# sch_version2.net
KiCad netlist of a schematic drawn in Altium Designer
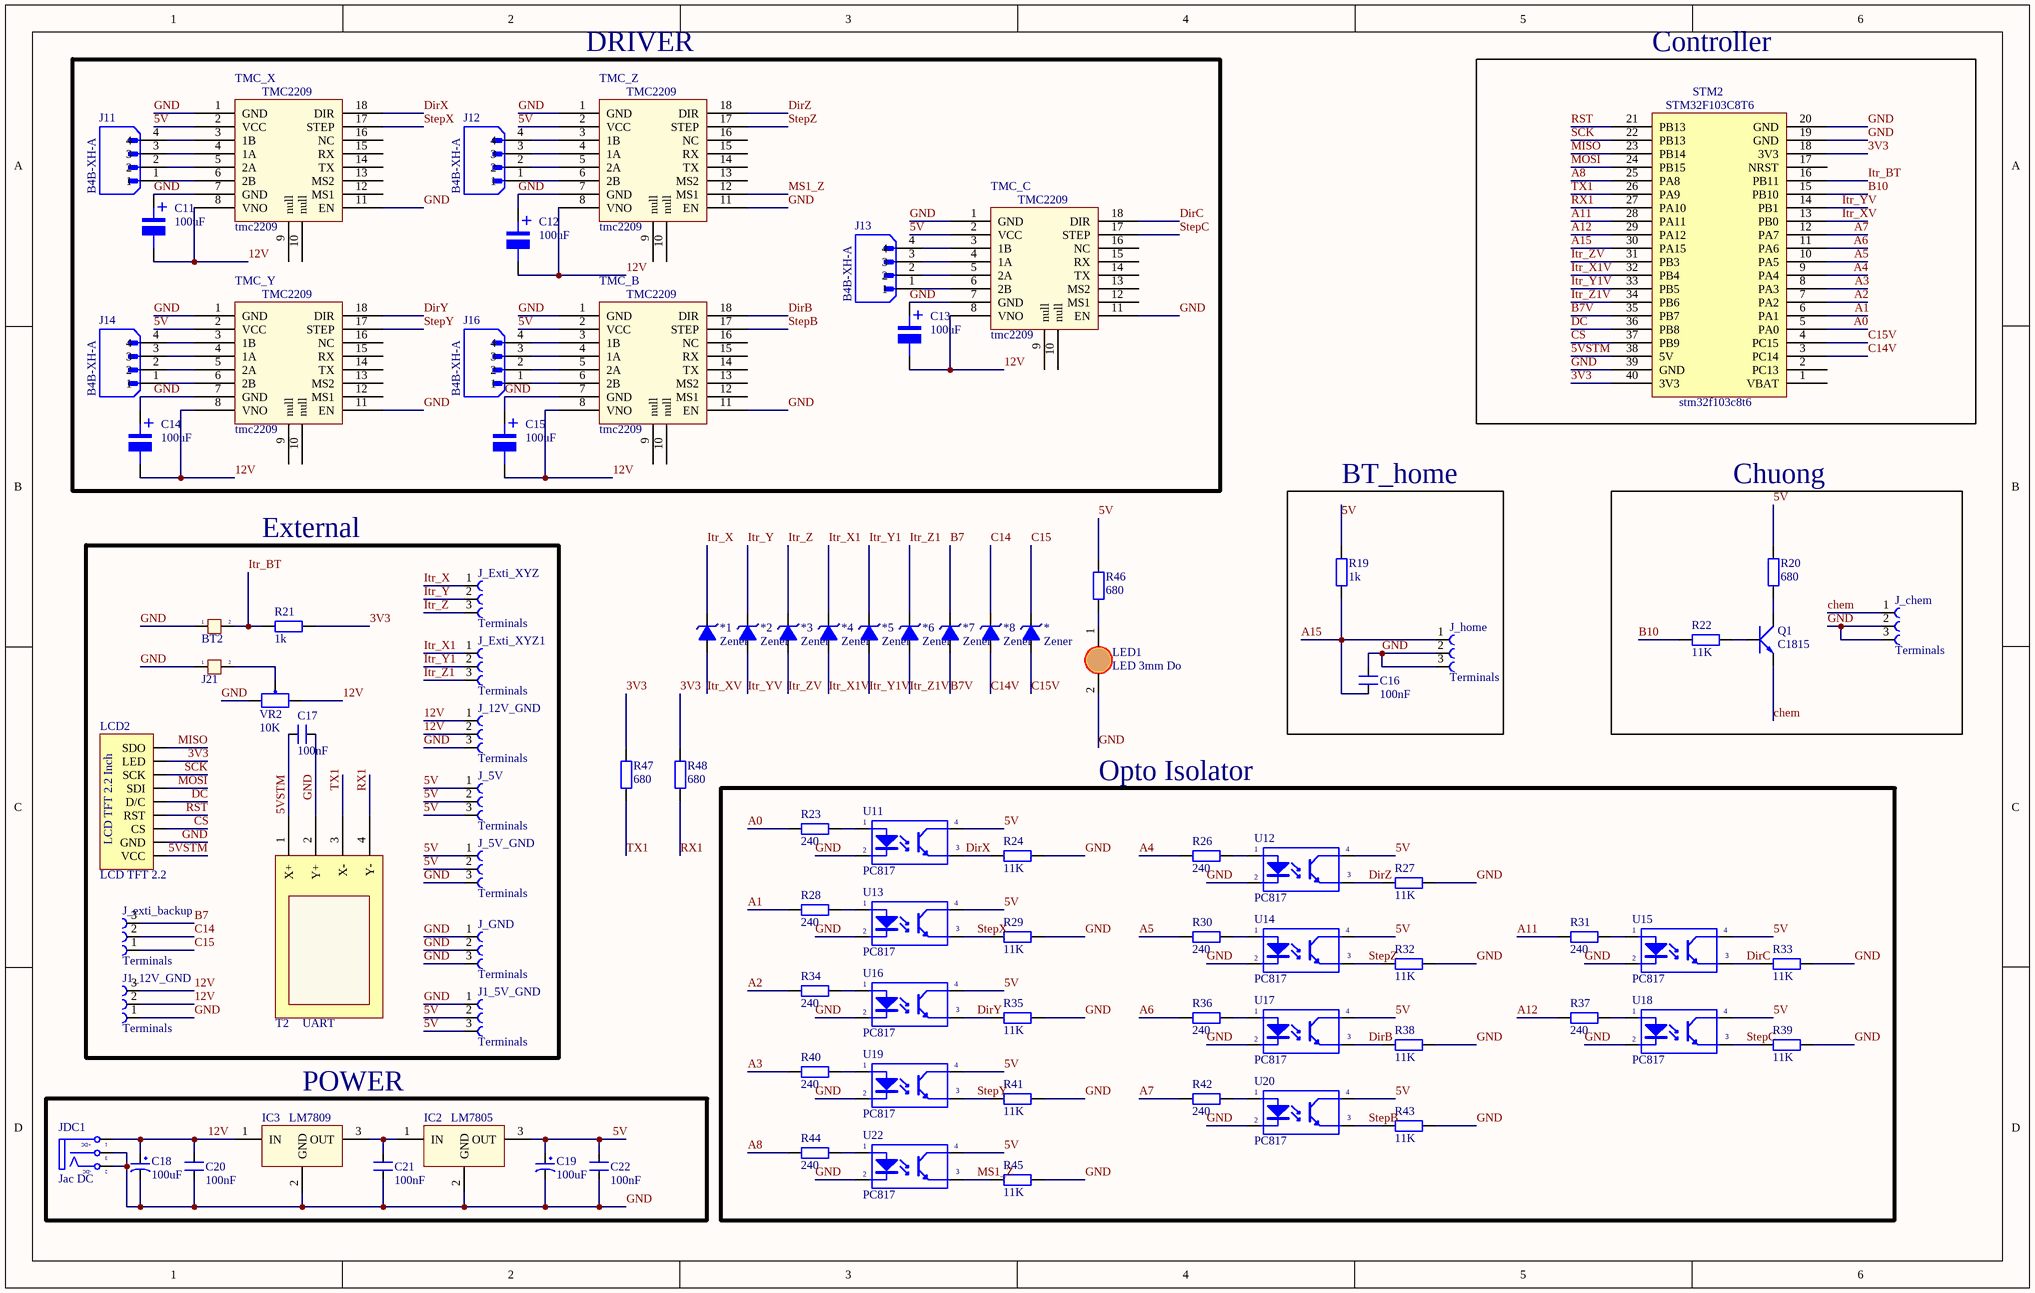
[diagram p0: sch_version2.SchDoc]

(export (version "E")
  (design (tool "Eeschema 10.0.6"))
  (components
    (comp (ref "*") (value "Zener") (footprint "D1A") (libsource (lib "syhaunguyen") (part "Zener")))
    (comp (ref "*1") (value "Zener") (footprint "D1A") (libsource (lib "syhaunguyen") (part "Zener")))
    (comp (ref "*2") (value "Zener") (footprint "D1A") (libsource (lib "syhaunguyen") (part "Zener")))
    (comp (ref "*3") (value "Zener") (footprint "D1A") (libsource (lib "syhaunguyen") (part "Zener")))
    (comp (ref "*4") (value "Zener") (footprint "D1A") (libsource (lib "syhaunguyen") (part "Zener")))
    (comp (ref "*5") (value "Zener") (footprint "D1A") (libsource (lib "syhaunguyen") (part "Zener")))
    (comp (ref "*6") (value "Zener") (footprint "D1A") (libsource (lib "syhaunguyen") (part "Zener")))
    (comp (ref "*7") (value "Zener") (footprint "D1A") (libsource (lib "syhaunguyen") (part "Zener")))
    (comp (ref "*8") (value "Zener") (footprint "D1A") (libsource (lib "syhaunguyen") (part "Zener")))
    (comp (ref "BT2") (value "Jumper 2") (footprint "jp2h") (libsource (lib "My Library") (part "JP 2")))
    (comp (ref "C11")
      (value "100uF")
      (footprint "tu nhom 6.3 (d)")
      (description "Dán")
      (libsource (lib "THU VIEN SCH") (part "Tu Nhom 100uF 16V"))
    )
    (comp (ref "C12")
      (value "100uF")
      (footprint "tu nhom 6.3 (d)")
      (description "Dán")
      (libsource (lib "THU VIEN SCH") (part "Tu Nhom 100uF 16V"))
    )
    (comp (ref "C13")
      (value "100uF")
      (footprint "tu nhom 6.3 (d)")
      (description "Dán")
      (libsource (lib "THU VIEN SCH") (part "Tu Nhom 100uF 16V"))
    )
    (comp (ref "C14")
      (value "100uF")
      (footprint "tu nhom 6.3 (d)")
      (description "Dán")
      (libsource (lib "THU VIEN SCH") (part "Tu Nhom 100uF 16V"))
    )
    (comp (ref "C15")
      (value "100uF")
      (footprint "tu nhom 6.3 (d)")
      (description "Dán")
      (libsource (lib "THU VIEN SCH") (part "Tu Nhom 100uF 16V"))
    )
    (comp (ref "C16")
      (value "100nF")
      (footprint "CN2")
      (description "Cap np 104 => 105pF")
      (libsource (lib "My Library") (part "CN2"))
    )
    (comp (ref "C17")
      (value "100nF")
      (footprint "CN2")
      (description "Cap np 104 => 105pF")
      (libsource (lib "My Library") (part "CN2"))
    )
    (comp (ref "C18")
      (value "100uF")
      (footprint "CP1.5/3.4")
      (description "Cap 100uF/35V - 470uF/16V")
      (libsource (lib "My Library") (part "CP3"))
    )
    (comp (ref "C19")
      (value "100uF")
      (footprint "CP1.5/3.4")
      (description "Cap 100uF/35V - 470uF/16V")
      (libsource (lib "My Library") (part "CP3"))
    )
    (comp (ref "C20")
      (value "100nF")
      (footprint "CN2")
      (description "Cap np 104 => 105pF")
      (libsource (lib "My Library") (part "CN2"))
    )
    (comp (ref "C21")
      (value "100nF")
      (footprint "CN2")
      (description "Cap np 104 => 105pF")
      (libsource (lib "My Library") (part "CN2"))
    )
    (comp (ref "C22")
      (value "100nF")
      (footprint "CN2")
      (description "Cap np 104 => 105pF")
      (libsource (lib "My Library") (part "CN2"))
    )
    (comp (ref "IC2")
      (value "LM7805")
      (footprint "QTO-220")
      (description "On ap +, from + 5 to + 24VDC")
      (libsource (lib "My Library") (part "LM78xx"))
    )
    (comp (ref "IC3")
      (value "LM7809")
      (footprint "QTO-220")
      (description "On ap +, from + 5 to + 24VDC")
      (libsource (lib "My Library") (part "LM78xx"))
    )
    (comp (ref "J1_5V_GND")
      (value "Terminals")
      (footprint "691214110003")
      (description "3 Position Wire to Board Terminal Block Horizontal with Board 0.138 (3.50mm) Through Hole")
      (fields (field (name "MP") "691214110003") (field (name "MF") "Wurth Elektronik"))
      (libsource (lib "691214110003") (part "691214110003"))
    )
    (comp (ref "J1_12V_GND")
      (value "Terminals")
      (footprint "691214110003")
      (description "3 Position Wire to Board Terminal Block Horizontal with Board 0.138 (3.50mm) Through Hole")
      (fields (field (name "MP") "691214110003") (field (name "MF") "Wurth Elektronik"))
      (libsource (lib "691214110003") (part "691214110003"))
    )
    (comp (ref "J11")
      (value "B4B-XH-A")
      (footprint "JST_B4B-XH-A(LF)(SN)")
      (fields (field (name "MP") "B4B-XH-A(LF)(SN)"))
      (libsource (lib "B4B-XH-A_LF__SN_") (part "B4B-XH-A(LF)(SN)"))
    )
    (comp (ref "J12")
      (value "B4B-XH-A")
      (footprint "JST_B4B-XH-A(LF)(SN)")
      (fields (field (name "MP") "B4B-XH-A(LF)(SN)"))
      (libsource (lib "B4B-XH-A_LF__SN_") (part "B4B-XH-A(LF)(SN)"))
    )
    (comp (ref "J13")
      (value "B4B-XH-A")
      (footprint "JST_B4B-XH-A(LF)(SN)")
      (fields (field (name "MP") "B4B-XH-A(LF)(SN)"))
      (libsource (lib "B4B-XH-A_LF__SN_") (part "B4B-XH-A(LF)(SN)"))
    )
    (comp (ref "J14")
      (value "B4B-XH-A")
      (footprint "JST_B4B-XH-A(LF)(SN)")
      (fields (field (name "MP") "B4B-XH-A(LF)(SN)"))
      (libsource (lib "B4B-XH-A_LF__SN_") (part "B4B-XH-A(LF)(SN)"))
    )
    (comp (ref "J16")
      (value "B4B-XH-A")
      (footprint "JST_B4B-XH-A(LF)(SN)")
      (fields (field (name "MP") "B4B-XH-A(LF)(SN)"))
      (libsource (lib "B4B-XH-A_LF__SN_") (part "B4B-XH-A(LF)(SN)"))
    )
    (comp (ref "J21") (value "Jumper 2") (footprint "jp2h") (libsource (lib "syhaunguyen") (part "JP 2")))
    (comp (ref "JDC1")
      (value "Jac DC")
      (footprint "DC-IN")
      (description "Jac DC input")
      (libsource (lib "My Library") (part "DCIN"))
    )
    (comp (ref "J_5V")
      (value "Terminals")
      (footprint "691214110003")
      (description "3 Position Wire to Board Terminal Block Horizontal with Board 0.138 (3.50mm) Through Hole")
      (fields (field (name "MP") "691214110003") (field (name "MF") "Wurth Elektronik"))
      (libsource (lib "691214110003") (part "691214110003"))
    )
    (comp (ref "J_5V_GND")
      (value "Terminals")
      (footprint "691214110003")
      (description "3 Position Wire to Board Terminal Block Horizontal with Board 0.138 (3.50mm) Through Hole")
      (fields (field (name "MP") "691214110003") (field (name "MF") "Wurth Elektronik"))
      (libsource (lib "691214110003") (part "691214110003"))
    )
    (comp (ref "J_12V_GND")
      (value "Terminals")
      (footprint "691214110003")
      (description "3 Position Wire to Board Terminal Block Horizontal with Board 0.138 (3.50mm) Through Hole")
      (fields (field (name "MP") "691214110003") (field (name "MF") "Wurth Elektronik"))
      (libsource (lib "691214110003") (part "691214110003"))
    )
    (comp (ref "J_chem")
      (value "Terminals")
      (footprint "691214110003")
      (description "3 Position Wire to Board Terminal Block Horizontal with Board 0.138 (3.50mm) Through Hole")
      (fields (field (name "MP") "691214110003") (field (name "MF") "Wurth Elektronik"))
      (libsource (lib "691214110003") (part "691214110003"))
    )
    (comp (ref "J_exti_backup")
      (value "Terminals")
      (footprint "691214110003")
      (description "3 Position Wire to Board Terminal Block Horizontal with Board 0.138 (3.50mm) Through Hole")
      (fields (field (name "MP") "691214110003") (field (name "MF") "Wurth Elektronik"))
      (libsource (lib "691214110003") (part "691214110003"))
    )
    (comp (ref "J_Exti_XYZ")
      (value "Terminals")
      (footprint "691214110003")
      (description "3 Position Wire to Board Terminal Block Horizontal with Board 0.138 (3.50mm) Through Hole")
      (fields (field (name "MP") "691214110003") (field (name "MF") "Wurth Elektronik"))
      (libsource (lib "691214110003") (part "691214110003"))
    )
    (comp (ref "J_Exti_XYZ1")
      (value "Terminals")
      (footprint "691214110003")
      (description "3 Position Wire to Board Terminal Block Horizontal with Board 0.138 (3.50mm) Through Hole")
      (fields (field (name "MP") "691214110003") (field (name "MF") "Wurth Elektronik"))
      (libsource (lib "691214110003") (part "691214110003"))
    )
    (comp (ref "J_GND")
      (value "Terminals")
      (footprint "691214110003")
      (description "3 Position Wire to Board Terminal Block Horizontal with Board 0.138 (3.50mm) Through Hole")
      (fields (field (name "MP") "691214110003") (field (name "MF") "Wurth Elektronik"))
      (libsource (lib "691214110003") (part "691214110003"))
    )
    (comp (ref "J_home")
      (value "Terminals")
      (footprint "691214110003")
      (description "3 Position Wire to Board Terminal Block Horizontal with Board 0.138 (3.50mm) Through Hole")
      (fields (field (name "MP") "691214110003") (field (name "MF") "Wurth Elektronik"))
      (libsource (lib "691214110003") (part "691214110003"))
    )
    (comp (ref "LCD2")
      (value "LCD TFT 2.2")
      (footprint "JP9-C1T")
      (fields
        (field (name "MANUFACTURER") "Würth Elektronik eiSos GmbH")
        (field (name "PARTNO") "613009143121")
        (field (name "CREATED BY") "Karrer Zheng")
      )
      (libsource (lib "My Library") (part "LCD TFT 2.2"))
    )
    (comp (ref "LED1")
      (value "LED 3mm Do")
      (footprint "LED 3mm Do")
      (description "Cắm")
      (libsource (lib "THU VIEN SCH") (part "LED 3mm Do"))
    )
    (comp (ref "Q1")
      (value "C1815")
      (footprint "QTO-92")
      (description "NPN 600mW, ECB")
      (libsource (lib "syhaunguyen") (part "C1815"))
    )
    (comp (ref "R19")
      (value "1k")
      (footprint "R1/4W")
      (description "Resistor 1/4W")
      (libsource (lib "My Library") (part "R1/4W"))
    )
    (comp (ref "R20")
      (value "680")
      (footprint "R1/4W")
      (description "Resistor 1/4W")
      (libsource (lib "My Library") (part "R1/4W"))
    )
    (comp (ref "R21")
      (value "1k")
      (footprint "R1/4W")
      (description "Resistor 1/4W")
      (libsource (lib "My Library") (part "R1/4W"))
    )
    (comp (ref "R22")
      (value "11K")
      (footprint "R1/4W")
      (description "Resistor 1/4W")
      (libsource (lib "My Library") (part "R1/4W"))
    )
    (comp (ref "R23")
      (value "240")
      (footprint "R1/4W")
      (description "Resistor 1/4W")
      (libsource (lib "My Library") (part "R1/4W"))
    )
    (comp (ref "R24")
      (value "11K")
      (footprint "R1/4W")
      (description "Resistor 1/4W")
      (libsource (lib "My Library") (part "R1/4W"))
    )
    (comp (ref "R26")
      (value "240")
      (footprint "R1/4W")
      (description "Resistor 1/4W")
      (libsource (lib "My Library") (part "R1/4W"))
    )
    (comp (ref "R27")
      (value "11K")
      (footprint "R1/4W")
      (description "Resistor 1/4W")
      (libsource (lib "My Library") (part "R1/4W"))
    )
    (comp (ref "R28")
      (value "240")
      (footprint "R1/4W")
      (description "Resistor 1/4W")
      (libsource (lib "My Library") (part "R1/4W"))
    )
    (comp (ref "R29")
      (value "11K")
      (footprint "R1/4W")
      (description "Resistor 1/4W")
      (libsource (lib "My Library") (part "R1/4W"))
    )
    (comp (ref "R30")
      (value "240")
      (footprint "R1/4W")
      (description "Resistor 1/4W")
      (libsource (lib "My Library") (part "R1/4W"))
    )
    (comp (ref "R31")
      (value "240")
      (footprint "R1/4W")
      (description "Resistor 1/4W")
      (libsource (lib "My Library") (part "R1/4W"))
    )
    (comp (ref "R32")
      (value "11K")
      (footprint "R1/4W")
      (description "Resistor 1/4W")
      (libsource (lib "My Library") (part "R1/4W"))
    )
    (comp (ref "R33")
      (value "11K")
      (footprint "R1/4W")
      (description "Resistor 1/4W")
      (libsource (lib "My Library") (part "R1/4W"))
    )
    (comp (ref "R34")
      (value "240")
      (footprint "R1/4W")
      (description "Resistor 1/4W")
      (libsource (lib "My Library") (part "R1/4W"))
    )
    (comp (ref "R35")
      (value "11K")
      (footprint "R1/4W")
      (description "Resistor 1/4W")
      (libsource (lib "My Library") (part "R1/4W"))
    )
    (comp (ref "R36")
      (value "240")
      (footprint "R1/4W")
      (description "Resistor 1/4W")
      (libsource (lib "My Library") (part "R1/4W"))
    )
    (comp (ref "R37")
      (value "240")
      (footprint "R1/4W")
      (description "Resistor 1/4W")
      (libsource (lib "My Library") (part "R1/4W"))
    )
    (comp (ref "R38")
      (value "11K")
      (footprint "R1/4W")
      (description "Resistor 1/4W")
      (libsource (lib "My Library") (part "R1/4W"))
    )
    (comp (ref "R39")
      (value "11K")
      (footprint "R1/4W")
      (description "Resistor 1/4W")
      (libsource (lib "My Library") (part "R1/4W"))
    )
    (comp (ref "R40")
      (value "240")
      (footprint "R1/4W")
      (description "Resistor 1/4W")
      (libsource (lib "My Library") (part "R1/4W"))
    )
    (comp (ref "R41")
      (value "11K")
      (footprint "R1/4W")
      (description "Resistor 1/4W")
      (libsource (lib "My Library") (part "R1/4W"))
    )
    (comp (ref "R42")
      (value "240")
      (footprint "R1/4W")
      (description "Resistor 1/4W")
      (libsource (lib "My Library") (part "R1/4W"))
    )
    (comp (ref "R43")
      (value "11K")
      (footprint "R1/4W")
      (description "Resistor 1/4W")
      (libsource (lib "My Library") (part "R1/4W"))
    )
    (comp (ref "R44")
      (value "240")
      (footprint "R1/4W")
      (description "Resistor 1/4W")
      (libsource (lib "My Library") (part "R1/4W"))
    )
    (comp (ref "R45")
      (value "11K")
      (footprint "R1/4W")
      (description "Resistor 1/4W")
      (libsource (lib "My Library") (part "R1/4W"))
    )
    (comp (ref "R46")
      (value "680")
      (footprint "R1/4W")
      (description "Resistor 1/4W")
      (libsource (lib "My Library") (part "R1/4W"))
    )
    (comp (ref "R47")
      (value "680")
      (footprint "R1/4W")
      (description "Resistor 1/4W")
      (libsource (lib "My Library") (part "R1/4W"))
    )
    (comp (ref "R48")
      (value "680")
      (footprint "R1/4W")
      (description "Resistor 1/4W")
      (libsource (lib "My Library") (part "R1/4W"))
    )
    (comp (ref "STM2")
      (value "stm32f103c8t6")
      (footprint "STM32F103")
      (libsource (lib "STM32F103") (part "STM32F103"))
    )
    (comp (ref "T2")
      (value "UART")
      (footprint "HDR1X4H")
      (description "4 wires")
      (fields (field (name "CREATOR") "Nguyen Ba Bien"))
      (libsource (lib "My Library") (part "TouchPanel"))
    )
    (comp (ref "TMC_B")
      (value "tmc2209")
      (footprint "TMC2209")
      (libsource (lib "tmc2209") (part "Driver_TMC2209"))
    )
    (comp (ref "TMC_C")
      (value "tmc2209")
      (footprint "TMC2209")
      (libsource (lib "tmc2209") (part "Driver_TMC2209"))
    )
    (comp (ref "TMC_X")
      (value "tmc2209")
      (footprint "TMC2209")
      (libsource (lib "tmc2209") (part "Driver_TMC2209"))
    )
    (comp (ref "TMC_Y")
      (value "tmc2209")
      (footprint "TMC2209")
      (libsource (lib "tmc2209") (part "Driver_TMC2209"))
    )
    (comp (ref "TMC_Z")
      (value "tmc2209")
      (footprint "TMC2209")
      (libsource (lib "tmc2209") (part "Driver_TMC2209"))
    )
    (comp (ref "U11")
      (value "PC817")
      (footprint "DIP4/W0.3")
      (description "Single Opto")
      (libsource (lib "syhaunguyen") (part "PC817"))
    )
    (comp (ref "U12")
      (value "PC817")
      (footprint "DIP4/W0.3")
      (description "Single Opto")
      (libsource (lib "syhaunguyen") (part "PC817"))
    )
    (comp (ref "U13")
      (value "PC817")
      (footprint "DIP4/W0.3")
      (description "Single Opto")
      (libsource (lib "syhaunguyen") (part "PC817"))
    )
    (comp (ref "U14")
      (value "PC817")
      (footprint "DIP4/W0.3")
      (description "Single Opto")
      (libsource (lib "syhaunguyen") (part "PC817"))
    )
    (comp (ref "U15")
      (value "PC817")
      (footprint "DIP4/W0.3")
      (description "Single Opto")
      (libsource (lib "syhaunguyen") (part "PC817"))
    )
    (comp (ref "U16")
      (value "PC817")
      (footprint "DIP4/W0.3")
      (description "Single Opto")
      (libsource (lib "syhaunguyen") (part "PC817"))
    )
    (comp (ref "U17")
      (value "PC817")
      (footprint "DIP4/W0.3")
      (description "Single Opto")
      (libsource (lib "syhaunguyen") (part "PC817"))
    )
    (comp (ref "U18")
      (value "PC817")
      (footprint "DIP4/W0.3")
      (description "Single Opto")
      (libsource (lib "syhaunguyen") (part "PC817"))
    )
    (comp (ref "U19")
      (value "PC817")
      (footprint "DIP4/W0.3")
      (description "Single Opto")
      (libsource (lib "syhaunguyen") (part "PC817"))
    )
    (comp (ref "U20")
      (value "PC817")
      (footprint "DIP4/W0.3")
      (description "Single Opto")
      (libsource (lib "syhaunguyen") (part "PC817"))
    )
    (comp (ref "U22")
      (value "PC817")
      (footprint "DIP4/W0.3")
      (description "Single Opto")
      (libsource (lib "syhaunguyen") (part "PC817"))
    )
    (comp (ref "VR2")
      (value "10K")
      (footprint "VR")
      (description "Var Resistor")
      (libsource (lib "syhaunguyen") (part "VR"))
    )
  )
  (nets
    (net (code "1") (name "/3V3") (class "Default")
      (node (ref "LCD2") (pin "8") (pinfunction "LED_8") (pintype "passive"))
      (node (ref "R21") (pin "2") (pinfunction "2_2") (pintype "passive"))
      (node (ref "R47") (pin "2") (pinfunction "2_2") (pintype "passive"))
      (node (ref "R48") (pin "2") (pinfunction "2_2") (pintype "passive"))
      (node (ref "STM2") (pin "18") (pinfunction "3V3_18") (pintype "passive"))
      (node (ref "STM2") (pin "40") (pinfunction "3V3_40") (pintype "passive"))
    )
    (net (code "2") (name "/5V") (class "Default")
      (node (ref "C19") (pin "1") (pinfunction "1_1") (pintype "passive"))
      (node (ref "C22") (pin "2") (pinfunction "2_2") (pintype "passive"))
      (node (ref "IC2") (pin "3") (pinfunction "OUT_3") (pintype "passive"))
      (node (ref "J1_5V_GND") (pin "2") (pinfunction "2_2") (pintype "passive"))
      (node (ref "J1_5V_GND") (pin "3") (pinfunction "3_3") (pintype "passive"))
      (node (ref "J_5V") (pin "1") (pinfunction "1_1") (pintype "passive"))
      (node (ref "J_5V") (pin "2") (pinfunction "2_2") (pintype "passive"))
      (node (ref "J_5V") (pin "3") (pinfunction "3_3") (pintype "passive"))
      (node (ref "J_5V_GND") (pin "1") (pinfunction "1_1") (pintype "passive"))
      (node (ref "J_5V_GND") (pin "2") (pinfunction "2_2") (pintype "passive"))
      (node (ref "R19") (pin "2") (pinfunction "2_2") (pintype "passive"))
      (node (ref "R20") (pin "2") (pinfunction "2_2") (pintype "passive"))
      (node (ref "R46") (pin "2") (pinfunction "2_2") (pintype "passive"))
      (node (ref "TMC_B") (pin "2") (pinfunction "VCC_2") (pintype "passive"))
      (node (ref "TMC_C") (pin "2") (pinfunction "VCC_2") (pintype "passive"))
      (node (ref "TMC_X") (pin "2") (pinfunction "VCC_2") (pintype "passive"))
      (node (ref "TMC_Y") (pin "2") (pinfunction "VCC_2") (pintype "passive"))
      (node (ref "TMC_Z") (pin "2") (pinfunction "VCC_2") (pintype "passive"))
      (node (ref "U11") (pin "4") (pinfunction "C_4") (pintype "passive"))
      (node (ref "U12") (pin "4") (pinfunction "C_4") (pintype "passive"))
      (node (ref "U13") (pin "4") (pinfunction "C_4") (pintype "passive"))
      (node (ref "U14") (pin "4") (pinfunction "C_4") (pintype "passive"))
      (node (ref "U15") (pin "4") (pinfunction "C_4") (pintype "passive"))
      (node (ref "U16") (pin "4") (pinfunction "C_4") (pintype "passive"))
      (node (ref "U17") (pin "4") (pinfunction "C_4") (pintype "passive"))
      (node (ref "U18") (pin "4") (pinfunction "C_4") (pintype "passive"))
      (node (ref "U19") (pin "4") (pinfunction "C_4") (pintype "passive"))
      (node (ref "U20") (pin "4") (pinfunction "C_4") (pintype "passive"))
      (node (ref "U22") (pin "4") (pinfunction "C_4") (pintype "passive"))
    )
    (net (code "3") (name "/5VSTM") (class "Default")
      (node (ref "C17") (pin "2") (pinfunction "2_2") (pintype "passive"))
      (node (ref "LCD2") (pin "1") (pinfunction "VCC_1") (pintype "passive"))
      (node (ref "STM2") (pin "38") (pinfunction "5V_38") (pintype "passive"))
      (node (ref "T2") (pin "1") (pinfunction "X+_1") (pintype "passive"))
    )
    (net (code "4") (name "/12V") (class "Default")
      (node (ref "C11") (pin "2") (pinfunction "2_2") (pintype "passive"))
      (node (ref "C12") (pin "2") (pinfunction "2_2") (pintype "passive"))
      (node (ref "C13") (pin "2") (pinfunction "2_2") (pintype "passive"))
      (node (ref "C14") (pin "2") (pinfunction "2_2") (pintype "passive"))
      (node (ref "C15") (pin "2") (pinfunction "2_2") (pintype "passive"))
      (node (ref "C18") (pin "1") (pinfunction "1_1") (pintype "passive"))
      (node (ref "C20") (pin "2") (pinfunction "2_2") (pintype "passive"))
      (node (ref "IC3") (pin "1") (pinfunction "IN_1") (pintype "passive"))
      (node (ref "J1_12V_GND") (pin "2") (pinfunction "2_2") (pintype "passive"))
      (node (ref "J1_12V_GND") (pin "3") (pinfunction "3_3") (pintype "passive"))
      (node (ref "JDC1") (pin "1") (pinfunction "T_1") (pintype "passive"))
      (node (ref "J_12V_GND") (pin "1") (pinfunction "1_1") (pintype "passive"))
      (node (ref "J_12V_GND") (pin "2") (pinfunction "2_2") (pintype "passive"))
      (node (ref "TMC_B") (pin "8") (pinfunction "VNO_8") (pintype "passive"))
      (node (ref "TMC_C") (pin "8") (pinfunction "VNO_8") (pintype "passive"))
      (node (ref "TMC_X") (pin "8") (pinfunction "VNO_8") (pintype "passive"))
      (node (ref "TMC_Y") (pin "8") (pinfunction "VNO_8") (pintype "passive"))
      (node (ref "TMC_Z") (pin "8") (pinfunction "VNO_8") (pintype "passive"))
      (node (ref "VR2") (pin "3") (pinfunction "3_3") (pintype "passive"))
    )
    (net (code "5") (name "/A0") (class "Default")
      (node (ref "R23") (pin "1") (pinfunction "1_1") (pintype "passive"))
      (node (ref "STM2") (pin "5") (pinfunction "PA0_5") (pintype "passive"))
    )
    (net (code "6") (name "/A1") (class "Default")
      (node (ref "R28") (pin "1") (pinfunction "1_1") (pintype "passive"))
      (node (ref "STM2") (pin "6") (pinfunction "PA1_6") (pintype "passive"))
    )
    (net (code "7") (name "/A2") (class "Default")
      (node (ref "R34") (pin "1") (pinfunction "1_1") (pintype "passive"))
      (node (ref "STM2") (pin "7") (pinfunction "PA2_7") (pintype "passive"))
    )
    (net (code "8") (name "/A3") (class "Default")
      (node (ref "R40") (pin "1") (pinfunction "1_1") (pintype "passive"))
      (node (ref "STM2") (pin "8") (pinfunction "PA3_8") (pintype "passive"))
    )
    (net (code "9") (name "/A4") (class "Default")
      (node (ref "R26") (pin "1") (pinfunction "1_1") (pintype "passive"))
      (node (ref "STM2") (pin "9") (pinfunction "PA4_9") (pintype "passive"))
    )
    (net (code "10") (name "/A5") (class "Default")
      (node (ref "R30") (pin "1") (pinfunction "1_1") (pintype "passive"))
      (node (ref "STM2") (pin "10") (pinfunction "PA5_10") (pintype "passive"))
    )
    (net (code "11") (name "/A6") (class "Default")
      (node (ref "R36") (pin "1") (pinfunction "1_1") (pintype "passive"))
      (node (ref "STM2") (pin "11") (pinfunction "PA6_11") (pintype "passive"))
    )
    (net (code "12") (name "/A7") (class "Default")
      (node (ref "R42") (pin "1") (pinfunction "1_1") (pintype "passive"))
      (node (ref "STM2") (pin "12") (pinfunction "PA7_12") (pintype "passive"))
    )
    (net (code "13") (name "/A8") (class "Default")
      (node (ref "R44") (pin "1") (pinfunction "1_1") (pintype "passive"))
      (node (ref "STM2") (pin "25") (pinfunction "PA8_25") (pintype "passive"))
    )
    (net (code "14") (name "/A11") (class "Default")
      (node (ref "R31") (pin "1") (pinfunction "1_1") (pintype "passive"))
      (node (ref "STM2") (pin "28") (pinfunction "PA11_28") (pintype "passive"))
    )
    (net (code "15") (name "/A12") (class "Default")
      (node (ref "R37") (pin "1") (pinfunction "1_1") (pintype "passive"))
      (node (ref "STM2") (pin "29") (pinfunction "PA12_29") (pintype "passive"))
    )
    (net (code "16") (name "/A15") (class "Default")
      (node (ref "C16") (pin "1") (pinfunction "1_1") (pintype "passive"))
      (node (ref "J_home") (pin "1") (pinfunction "1_1") (pintype "passive"))
      (node (ref "R19") (pin "1") (pinfunction "1_1") (pintype "passive"))
      (node (ref "STM2") (pin "30") (pinfunction "PA15_30") (pintype "passive"))
    )
    (net (code "17") (name "/B7") (class "Default")
      (node (ref "*7") (pin "2") (pinfunction "K_2") (pintype "passive"))
      (node (ref "J_exti_backup") (pin "3") (pinfunction "3_3") (pintype "passive"))
    )
    (net (code "18") (name "/B7V") (class "Default")
      (node (ref "*7") (pin "1") (pinfunction "A_1") (pintype "passive"))
      (node (ref "STM2") (pin "35") (pinfunction "PB7_35") (pintype "passive"))
    )
    (net (code "19") (name "/B10") (class "Default")
      (node (ref "R22") (pin "1") (pinfunction "1_1") (pintype "passive"))
      (node (ref "STM2") (pin "15") (pinfunction "PB10_15") (pintype "passive"))
    )
    (net (code "20") (name "/C14") (class "Default")
      (node (ref "*8") (pin "2") (pinfunction "K_2") (pintype "passive"))
      (node (ref "J_exti_backup") (pin "2") (pinfunction "2_2") (pintype "passive"))
    )
    (net (code "21") (name "/C14V") (class "Default")
      (node (ref "*8") (pin "1") (pinfunction "A_1") (pintype "passive"))
      (node (ref "STM2") (pin "3") (pinfunction "PC14_3") (pintype "passive"))
    )
    (net (code "22") (name "/C15") (class "Default")
      (node (ref "*") (pin "2") (pinfunction "K_2") (pintype "passive"))
      (node (ref "J_exti_backup") (pin "1") (pinfunction "1_1") (pintype "passive"))
    )
    (net (code "23") (name "/C15V") (class "Default")
      (node (ref "*") (pin "1") (pinfunction "A_1") (pintype "passive"))
      (node (ref "STM2") (pin "4") (pinfunction "PC15_4") (pintype "passive"))
    )
    (net (code "24") (name "/CS") (class "Default")
      (node (ref "LCD2") (pin "3") (pinfunction "CS_3") (pintype "passive"))
      (node (ref "STM2") (pin "37") (pinfunction "PB9_37") (pintype "passive"))
    )
    (net (code "25") (name "/DC") (class "Default")
      (node (ref "LCD2") (pin "5") (pinfunction "D/C_5") (pintype "passive"))
      (node (ref "STM2") (pin "36") (pinfunction "PB8_36") (pintype "passive"))
    )
    (net (code "26") (name "/DirB") (class "Default")
      (node (ref "R38") (pin "1") (pinfunction "1_1") (pintype "passive"))
      (node (ref "TMC_B") (pin "18") (pinfunction "DIR_18") (pintype "passive"))
      (node (ref "U17") (pin "3") (pinfunction "E_3") (pintype "passive"))
    )
    (net (code "27") (name "/DirC") (class "Default")
      (node (ref "R33") (pin "1") (pinfunction "1_1") (pintype "passive"))
      (node (ref "TMC_C") (pin "18") (pinfunction "DIR_18") (pintype "passive"))
      (node (ref "U15") (pin "3") (pinfunction "E_3") (pintype "passive"))
    )
    (net (code "28") (name "/DirX") (class "Default")
      (node (ref "R24") (pin "1") (pinfunction "1_1") (pintype "passive"))
      (node (ref "TMC_X") (pin "18") (pinfunction "DIR_18") (pintype "passive"))
      (node (ref "U11") (pin "3") (pinfunction "E_3") (pintype "passive"))
    )
    (net (code "29") (name "/DirY") (class "Default")
      (node (ref "R35") (pin "1") (pinfunction "1_1") (pintype "passive"))
      (node (ref "TMC_Y") (pin "18") (pinfunction "DIR_18") (pintype "passive"))
      (node (ref "U16") (pin "3") (pinfunction "E_3") (pintype "passive"))
    )
    (net (code "30") (name "/DirZ") (class "Default")
      (node (ref "R27") (pin "1") (pinfunction "1_1") (pintype "passive"))
      (node (ref "TMC_Z") (pin "18") (pinfunction "DIR_18") (pintype "passive"))
      (node (ref "U12") (pin "3") (pinfunction "E_3") (pintype "passive"))
    )
    (net (code "31") (name "/GND") (class "Default")
      (node (ref "BT2") (pin "1") (pinfunction "1_1") (pintype "passive"))
      (node (ref "C11") (pin "1") (pinfunction "1_1") (pintype "passive"))
      (node (ref "C12") (pin "1") (pinfunction "1_1") (pintype "passive"))
      (node (ref "C13") (pin "1") (pinfunction "1_1") (pintype "passive"))
      (node (ref "C14") (pin "1") (pinfunction "1_1") (pintype "passive"))
      (node (ref "C15") (pin "1") (pinfunction "1_1") (pintype "passive"))
      (node (ref "C16") (pin "2") (pinfunction "2_2") (pintype "passive"))
      (node (ref "C17") (pin "1") (pinfunction "1_1") (pintype "passive"))
      (node (ref "C18") (pin "2") (pinfunction "2_2") (pintype "passive"))
      (node (ref "C19") (pin "2") (pinfunction "2_2") (pintype "passive"))
      (node (ref "C20") (pin "1") (pinfunction "1_1") (pintype "passive"))
      (node (ref "C21") (pin "1") (pinfunction "1_1") (pintype "passive"))
      (node (ref "C22") (pin "1") (pinfunction "1_1") (pintype "passive"))
      (node (ref "IC2") (pin "2") (pinfunction "GND_2") (pintype "passive"))
      (node (ref "IC3") (pin "2") (pinfunction "GND_2") (pintype "passive"))
      (node (ref "J1_12V_GND") (pin "1") (pinfunction "1_1") (pintype "passive"))
      (node (ref "J1_5V_GND") (pin "1") (pinfunction "1_1") (pintype "passive"))
      (node (ref "J21") (pin "1") (pinfunction "1_1") (pintype "passive"))
      (node (ref "JDC1") (pin "2") (pinfunction "TN_2") (pintype "passive"))
      (node (ref "JDC1") (pin "3") (pinfunction "S_3") (pintype "power_in"))
      (node (ref "J_12V_GND") (pin "3") (pinfunction "3_3") (pintype "passive"))
      (node (ref "J_5V_GND") (pin "3") (pinfunction "3_3") (pintype "passive"))
      (node (ref "J_GND") (pin "1") (pinfunction "1_1") (pintype "passive"))
      (node (ref "J_GND") (pin "2") (pinfunction "2_2") (pintype "passive"))
      (node (ref "J_GND") (pin "3") (pinfunction "3_3") (pintype "passive"))
      (node (ref "J_chem") (pin "2") (pinfunction "2_2") (pintype "passive"))
      (node (ref "J_chem") (pin "3") (pinfunction "3_3") (pintype "passive"))
      (node (ref "J_home") (pin "2") (pinfunction "2_2") (pintype "passive"))
      (node (ref "J_home") (pin "3") (pinfunction "3_3") (pintype "passive"))
      (node (ref "LCD2") (pin "2") (pinfunction "GND_2") (pintype "passive"))
      (node (ref "LED1") (pin "2") (pinfunction "K_2") (pintype "passive"))
      (node (ref "R24") (pin "2") (pinfunction "2_2") (pintype "passive"))
      (node (ref "R27") (pin "2") (pinfunction "2_2") (pintype "passive"))
      (node (ref "R29") (pin "2") (pinfunction "2_2") (pintype "passive"))
      (node (ref "R32") (pin "2") (pinfunction "2_2") (pintype "passive"))
      (node (ref "R33") (pin "2") (pinfunction "2_2") (pintype "passive"))
      (node (ref "R35") (pin "2") (pinfunction "2_2") (pintype "passive"))
      (node (ref "R38") (pin "2") (pinfunction "2_2") (pintype "passive"))
      (node (ref "R39") (pin "2") (pinfunction "2_2") (pintype "passive"))
      (node (ref "R41") (pin "2") (pinfunction "2_2") (pintype "passive"))
      (node (ref "R43") (pin "2") (pinfunction "2_2") (pintype "passive"))
      (node (ref "R45") (pin "2") (pinfunction "2_2") (pintype "passive"))
      (node (ref "STM2") (pin "19") (pinfunction "GND_19") (pintype "passive"))
      (node (ref "STM2") (pin "20") (pinfunction "GND_20") (pintype "passive"))
      (node (ref "STM2") (pin "39") (pinfunction "GND_39") (pintype "passive"))
      (node (ref "T2") (pin "2") (pinfunction "Y+_2") (pintype "passive"))
      (node (ref "TMC_B") (pin "1") (pinfunction "GND_1") (pintype "passive"))
      (node (ref "TMC_B") (pin "11") (pinfunction "EN_11") (pintype "passive"))
      (node (ref "TMC_B") (pin "7") (pinfunction "GND_7") (pintype "passive"))
      (node (ref "TMC_C") (pin "1") (pinfunction "GND_1") (pintype "passive"))
      (node (ref "TMC_C") (pin "11") (pinfunction "EN_11") (pintype "passive"))
      (node (ref "TMC_C") (pin "7") (pinfunction "GND_7") (pintype "passive"))
      (node (ref "TMC_X") (pin "1") (pinfunction "GND_1") (pintype "passive"))
      (node (ref "TMC_X") (pin "11") (pinfunction "EN_11") (pintype "passive"))
      (node (ref "TMC_X") (pin "7") (pinfunction "GND_7") (pintype "passive"))
      (node (ref "TMC_Y") (pin "1") (pinfunction "GND_1") (pintype "passive"))
      (node (ref "TMC_Y") (pin "11") (pinfunction "EN_11") (pintype "passive"))
      (node (ref "TMC_Y") (pin "7") (pinfunction "GND_7") (pintype "passive"))
      (node (ref "TMC_Z") (pin "1") (pinfunction "GND_1") (pintype "passive"))
      (node (ref "TMC_Z") (pin "11") (pinfunction "EN_11") (pintype "passive"))
      (node (ref "TMC_Z") (pin "7") (pinfunction "GND_7") (pintype "passive"))
      (node (ref "U11") (pin "2") (pinfunction "K_2") (pintype "passive"))
      (node (ref "U12") (pin "2") (pinfunction "K_2") (pintype "passive"))
      (node (ref "U13") (pin "2") (pinfunction "K_2") (pintype "passive"))
      (node (ref "U14") (pin "2") (pinfunction "K_2") (pintype "passive"))
      (node (ref "U15") (pin "2") (pinfunction "K_2") (pintype "passive"))
      (node (ref "U16") (pin "2") (pinfunction "K_2") (pintype "passive"))
      (node (ref "U17") (pin "2") (pinfunction "K_2") (pintype "passive"))
      (node (ref "U18") (pin "2") (pinfunction "K_2") (pintype "passive"))
      (node (ref "U19") (pin "2") (pinfunction "K_2") (pintype "passive"))
      (node (ref "U20") (pin "2") (pinfunction "K_2") (pintype "passive"))
      (node (ref "U22") (pin "2") (pinfunction "K_2") (pintype "passive"))
      (node (ref "VR2") (pin "1") (pinfunction "1_1") (pintype "passive"))
    )
    (net (code "32") (name "/Itr_BT") (class "Default")
      (node (ref "BT2") (pin "2") (pinfunction "2_2") (pintype "passive"))
      (node (ref "R21") (pin "1") (pinfunction "1_1") (pintype "passive"))
      (node (ref "STM2") (pin "16") (pinfunction "PB11_16") (pintype "passive"))
    )
    (net (code "33") (name "/Itr_X") (class "Default")
      (node (ref "*1") (pin "2") (pinfunction "K_2") (pintype "passive"))
      (node (ref "J_Exti_XYZ") (pin "1") (pinfunction "1_1") (pintype "passive"))
    )
    (net (code "34") (name "/Itr_X1") (class "Default")
      (node (ref "*4") (pin "2") (pinfunction "K_2") (pintype "passive"))
      (node (ref "J_Exti_XYZ1") (pin "1") (pinfunction "1_1") (pintype "passive"))
    )
    (net (code "35") (name "/Itr_X1V") (class "Default")
      (node (ref "*4") (pin "1") (pinfunction "A_1") (pintype "passive"))
      (node (ref "STM2") (pin "32") (pinfunction "PB4_32") (pintype "passive"))
    )
    (net (code "36") (name "/Itr_XV") (class "Default")
      (node (ref "*1") (pin "1") (pinfunction "A_1") (pintype "passive"))
      (node (ref "STM2") (pin "13") (pinfunction "PB0_13") (pintype "passive"))
    )
    (net (code "37") (name "/Itr_Y") (class "Default")
      (node (ref "*2") (pin "2") (pinfunction "K_2") (pintype "passive"))
      (node (ref "J_Exti_XYZ") (pin "2") (pinfunction "2_2") (pintype "passive"))
    )
    (net (code "38") (name "/Itr_Y1") (class "Default")
      (node (ref "*5") (pin "2") (pinfunction "K_2") (pintype "passive"))
      (node (ref "J_Exti_XYZ1") (pin "2") (pinfunction "2_2") (pintype "passive"))
    )
    (net (code "39") (name "/Itr_Y1V") (class "Default")
      (node (ref "*5") (pin "1") (pinfunction "A_1") (pintype "passive"))
      (node (ref "STM2") (pin "33") (pinfunction "PB5_33") (pintype "passive"))
    )
    (net (code "40") (name "/Itr_YV") (class "Default")
      (node (ref "*2") (pin "1") (pinfunction "A_1") (pintype "passive"))
      (node (ref "STM2") (pin "14") (pinfunction "PB1_14") (pintype "passive"))
    )
    (net (code "41") (name "/Itr_Z") (class "Default")
      (node (ref "*3") (pin "2") (pinfunction "K_2") (pintype "passive"))
      (node (ref "J_Exti_XYZ") (pin "3") (pinfunction "3_3") (pintype "passive"))
    )
    (net (code "42") (name "/Itr_Z1") (class "Default")
      (node (ref "*6") (pin "2") (pinfunction "K_2") (pintype "passive"))
      (node (ref "J_Exti_XYZ1") (pin "3") (pinfunction "3_3") (pintype "passive"))
    )
    (net (code "43") (name "/Itr_Z1V") (class "Default")
      (node (ref "*6") (pin "1") (pinfunction "A_1") (pintype "passive"))
      (node (ref "STM2") (pin "34") (pinfunction "PB6_34") (pintype "passive"))
    )
    (net (code "44") (name "/Itr_ZV") (class "Default")
      (node (ref "*3") (pin "1") (pinfunction "A_1") (pintype "passive"))
      (node (ref "STM2") (pin "31") (pinfunction "PB3_31") (pintype "passive"))
    )
    (net (code "45") (name "/MISO") (class "Default")
      (node (ref "LCD2") (pin "9") (pinfunction "SDO_9") (pintype "passive"))
      (node (ref "STM2") (pin "23") (pinfunction "PB14_23") (pintype "passive"))
    )
    (net (code "46") (name "/MOSI") (class "Default")
      (node (ref "LCD2") (pin "6") (pinfunction "SDI_6") (pintype "passive"))
      (node (ref "STM2") (pin "24") (pinfunction "PB15_24") (pintype "passive"))
    )
    (net (code "47") (name "/MS1_Z") (class "Default")
      (node (ref "R45") (pin "1") (pinfunction "1_1") (pintype "passive"))
      (node (ref "TMC_Z") (pin "12") (pinfunction "MS1_12") (pintype "passive"))
      (node (ref "U22") (pin "3") (pinfunction "E_3") (pintype "passive"))
    )
    (net (code "48") (name "/RST") (class "Default")
      (node (ref "LCD2") (pin "4") (pinfunction "RST_4") (pintype "passive"))
      (node (ref "STM2") (pin "21") (pinfunction "PB13_21") (pintype "passive"))
    )
    (net (code "49") (name "/RX1") (class "Default")
      (node (ref "R48") (pin "1") (pinfunction "1_1") (pintype "passive"))
      (node (ref "STM2") (pin "27") (pinfunction "PA10_27") (pintype "passive"))
      (node (ref "T2") (pin "4") (pinfunction "Y-_4") (pintype "passive"))
    )
    (net (code "50") (name "/SCK") (class "Default")
      (node (ref "LCD2") (pin "7") (pinfunction "SCK_7") (pintype "passive"))
      (node (ref "STM2") (pin "22") (pinfunction "PB13_22") (pintype "passive"))
    )
    (net (code "51") (name "/StepB") (class "Default")
      (node (ref "R43") (pin "1") (pinfunction "1_1") (pintype "passive"))
      (node (ref "TMC_B") (pin "17") (pinfunction "STEP_17") (pintype "passive"))
      (node (ref "U20") (pin "3") (pinfunction "E_3") (pintype "passive"))
    )
    (net (code "52") (name "/StepC") (class "Default")
      (node (ref "R39") (pin "1") (pinfunction "1_1") (pintype "passive"))
      (node (ref "TMC_C") (pin "17") (pinfunction "STEP_17") (pintype "passive"))
      (node (ref "U18") (pin "3") (pinfunction "E_3") (pintype "passive"))
    )
    (net (code "53") (name "/StepX") (class "Default")
      (node (ref "R29") (pin "1") (pinfunction "1_1") (pintype "passive"))
      (node (ref "TMC_X") (pin "17") (pinfunction "STEP_17") (pintype "passive"))
      (node (ref "U13") (pin "3") (pinfunction "E_3") (pintype "passive"))
    )
    (net (code "54") (name "/StepY") (class "Default")
      (node (ref "R41") (pin "1") (pinfunction "1_1") (pintype "passive"))
      (node (ref "TMC_Y") (pin "17") (pinfunction "STEP_17") (pintype "passive"))
      (node (ref "U19") (pin "3") (pinfunction "E_3") (pintype "passive"))
    )
    (net (code "55") (name "/StepZ") (class "Default")
      (node (ref "R32") (pin "1") (pinfunction "1_1") (pintype "passive"))
      (node (ref "TMC_Z") (pin "17") (pinfunction "STEP_17") (pintype "passive"))
      (node (ref "U14") (pin "3") (pinfunction "E_3") (pintype "passive"))
    )
    (net (code "56") (name "/TX1") (class "Default")
      (node (ref "R47") (pin "1") (pinfunction "1_1") (pintype "passive"))
      (node (ref "STM2") (pin "26") (pinfunction "PA9_26") (pintype "passive"))
      (node (ref "T2") (pin "3") (pinfunction "X-_3") (pintype "passive"))
    )
    (net (code "57") (name "/chem") (class "Default")
      (node (ref "J_chem") (pin "1") (pinfunction "1_1") (pintype "passive"))
      (node (ref "Q1") (pin "1") (pinfunction "E_1") (pintype "passive"))
    )
    (net (code "58") (name "Net-(IC2-IN)") (class "Default")
      (node (ref "C21") (pin "2") (pinfunction "2_2") (pintype "passive"))
      (node (ref "IC2") (pin "1") (pinfunction "IN_1") (pintype "passive"))
      (node (ref "IC3") (pin "3") (pinfunction "OUT_3") (pintype "passive"))
    )
    (net (code "59") (name "Net-(J21-Pad2)") (class "Default")
      (node (ref "J21") (pin "2") (pinfunction "2_2") (pintype "passive"))
      (node (ref "VR2") (pin "2") (pinfunction "2_2") (pintype "passive"))
    )
    (net (code "60") (name "Net-(LED1-A)") (class "Default")
      (node (ref "LED1") (pin "1") (pinfunction "A_1") (pintype "passive"))
      (node (ref "R46") (pin "1") (pinfunction "1_1") (pintype "passive"))
    )
    (net (code "61") (name "Net-(Q1-B)") (class "Default")
      (node (ref "Q1") (pin "3") (pinfunction "B_3") (pintype "passive"))
      (node (ref "R22") (pin "2") (pinfunction "2_2") (pintype "passive"))
    )
    (net (code "62") (name "Net-(Q1-C)") (class "Default")
      (node (ref "Q1") (pin "2") (pinfunction "C_2") (pintype "passive"))
      (node (ref "R20") (pin "1") (pinfunction "1_1") (pintype "passive"))
    )
    (net (code "63") (name "Net-(TMC_B-1A)") (class "Default")
      (node (ref "J16") (pin "3") (pinfunction "3_3") (pintype "passive"))
      (node (ref "TMC_B") (pin "4") (pinfunction "1A_4") (pintype "passive"))
    )
    (net (code "64") (name "Net-(TMC_B-1B)") (class "Default")
      (node (ref "J16") (pin "4") (pinfunction "4_4") (pintype "passive"))
      (node (ref "TMC_B") (pin "3") (pinfunction "1B_3") (pintype "passive"))
    )
    (net (code "65") (name "Net-(TMC_B-2A)") (class "Default")
      (node (ref "J16") (pin "2") (pinfunction "2_2") (pintype "passive"))
      (node (ref "TMC_B") (pin "5") (pinfunction "2A_5") (pintype "passive"))
    )
    (net (code "66") (name "Net-(TMC_B-2B)") (class "Default")
      (node (ref "J16") (pin "1") (pinfunction "1_1") (pintype "passive"))
      (node (ref "TMC_B") (pin "6") (pinfunction "2B_6") (pintype "passive"))
    )
    (net (code "67") (name "Net-(TMC_C-1A)") (class "Default")
      (node (ref "J13") (pin "3") (pinfunction "3_3") (pintype "passive"))
      (node (ref "TMC_C") (pin "4") (pinfunction "1A_4") (pintype "passive"))
    )
    (net (code "68") (name "Net-(TMC_C-1B)") (class "Default")
      (node (ref "J13") (pin "4") (pinfunction "4_4") (pintype "passive"))
      (node (ref "TMC_C") (pin "3") (pinfunction "1B_3") (pintype "passive"))
    )
    (net (code "69") (name "Net-(TMC_C-2A)") (class "Default")
      (node (ref "J13") (pin "2") (pinfunction "2_2") (pintype "passive"))
      (node (ref "TMC_C") (pin "5") (pinfunction "2A_5") (pintype "passive"))
    )
    (net (code "70") (name "Net-(TMC_C-2B)") (class "Default")
      (node (ref "J13") (pin "1") (pinfunction "1_1") (pintype "passive"))
      (node (ref "TMC_C") (pin "6") (pinfunction "2B_6") (pintype "passive"))
    )
    (net (code "71") (name "Net-(TMC_X-1A)") (class "Default")
      (node (ref "J11") (pin "3") (pinfunction "3_3") (pintype "passive"))
      (node (ref "TMC_X") (pin "4") (pinfunction "1A_4") (pintype "passive"))
    )
    (net (code "72") (name "Net-(TMC_X-1B)") (class "Default")
      (node (ref "J11") (pin "4") (pinfunction "4_4") (pintype "passive"))
      (node (ref "TMC_X") (pin "3") (pinfunction "1B_3") (pintype "passive"))
    )
    (net (code "73") (name "Net-(TMC_X-2A)") (class "Default")
      (node (ref "J11") (pin "2") (pinfunction "2_2") (pintype "passive"))
      (node (ref "TMC_X") (pin "5") (pinfunction "2A_5") (pintype "passive"))
    )
    (net (code "74") (name "Net-(TMC_X-2B)") (class "Default")
      (node (ref "J11") (pin "1") (pinfunction "1_1") (pintype "passive"))
      (node (ref "TMC_X") (pin "6") (pinfunction "2B_6") (pintype "passive"))
    )
    (net (code "75") (name "Net-(TMC_Y-1A)") (class "Default")
      (node (ref "J14") (pin "3") (pinfunction "3_3") (pintype "passive"))
      (node (ref "TMC_Y") (pin "4") (pinfunction "1A_4") (pintype "passive"))
    )
    (net (code "76") (name "Net-(TMC_Y-1B)") (class "Default")
      (node (ref "J14") (pin "4") (pinfunction "4_4") (pintype "passive"))
      (node (ref "TMC_Y") (pin "3") (pinfunction "1B_3") (pintype "passive"))
    )
    (net (code "77") (name "Net-(TMC_Y-2A)") (class "Default")
      (node (ref "J14") (pin "2") (pinfunction "2_2") (pintype "passive"))
      (node (ref "TMC_Y") (pin "5") (pinfunction "2A_5") (pintype "passive"))
    )
    (net (code "78") (name "Net-(TMC_Y-2B)") (class "Default")
      (node (ref "J14") (pin "1") (pinfunction "1_1") (pintype "passive"))
      (node (ref "TMC_Y") (pin "6") (pinfunction "2B_6") (pintype "passive"))
    )
    (net (code "79") (name "Net-(TMC_Z-1A)") (class "Default")
      (node (ref "J12") (pin "3") (pinfunction "3_3") (pintype "passive"))
      (node (ref "TMC_Z") (pin "4") (pinfunction "1A_4") (pintype "passive"))
    )
    (net (code "80") (name "Net-(TMC_Z-1B)") (class "Default")
      (node (ref "J12") (pin "4") (pinfunction "4_4") (pintype "passive"))
      (node (ref "TMC_Z") (pin "3") (pinfunction "1B_3") (pintype "passive"))
    )
    (net (code "81") (name "Net-(TMC_Z-2A)") (class "Default")
      (node (ref "J12") (pin "2") (pinfunction "2_2") (pintype "passive"))
      (node (ref "TMC_Z") (pin "5") (pinfunction "2A_5") (pintype "passive"))
    )
    (net (code "82") (name "Net-(TMC_Z-2B)") (class "Default")
      (node (ref "J12") (pin "1") (pinfunction "1_1") (pintype "passive"))
      (node (ref "TMC_Z") (pin "6") (pinfunction "2B_6") (pintype "passive"))
    )
    (net (code "83") (name "Net-(U11-A)") (class "Default")
      (node (ref "R23") (pin "2") (pinfunction "2_2") (pintype "passive"))
      (node (ref "U11") (pin "1") (pinfunction "A_1") (pintype "passive"))
    )
    (net (code "84") (name "Net-(U12-A)") (class "Default")
      (node (ref "R26") (pin "2") (pinfunction "2_2") (pintype "passive"))
      (node (ref "U12") (pin "1") (pinfunction "A_1") (pintype "passive"))
    )
    (net (code "85") (name "Net-(U13-A)") (class "Default")
      (node (ref "R28") (pin "2") (pinfunction "2_2") (pintype "passive"))
      (node (ref "U13") (pin "1") (pinfunction "A_1") (pintype "passive"))
    )
    (net (code "86") (name "Net-(U14-A)") (class "Default")
      (node (ref "R30") (pin "2") (pinfunction "2_2") (pintype "passive"))
      (node (ref "U14") (pin "1") (pinfunction "A_1") (pintype "passive"))
    )
    (net (code "87") (name "Net-(U15-A)") (class "Default")
      (node (ref "R31") (pin "2") (pinfunction "2_2") (pintype "passive"))
      (node (ref "U15") (pin "1") (pinfunction "A_1") (pintype "passive"))
    )
    (net (code "88") (name "Net-(U16-A)") (class "Default")
      (node (ref "R34") (pin "2") (pinfunction "2_2") (pintype "passive"))
      (node (ref "U16") (pin "1") (pinfunction "A_1") (pintype "passive"))
    )
    (net (code "89") (name "Net-(U17-A)") (class "Default")
      (node (ref "R36") (pin "2") (pinfunction "2_2") (pintype "passive"))
      (node (ref "U17") (pin "1") (pinfunction "A_1") (pintype "passive"))
    )
    (net (code "90") (name "Net-(U18-A)") (class "Default")
      (node (ref "R37") (pin "2") (pinfunction "2_2") (pintype "passive"))
      (node (ref "U18") (pin "1") (pinfunction "A_1") (pintype "passive"))
    )
    (net (code "91") (name "Net-(U19-A)") (class "Default")
      (node (ref "R40") (pin "2") (pinfunction "2_2") (pintype "passive"))
      (node (ref "U19") (pin "1") (pinfunction "A_1") (pintype "passive"))
    )
    (net (code "92") (name "Net-(U20-A)") (class "Default")
      (node (ref "R42") (pin "2") (pinfunction "2_2") (pintype "passive"))
      (node (ref "U20") (pin "1") (pinfunction "A_1") (pintype "passive"))
    )
    (net (code "93") (name "Net-(U22-A)") (class "Default")
      (node (ref "R44") (pin "2") (pinfunction "2_2") (pintype "passive"))
      (node (ref "U22") (pin "1") (pinfunction "A_1") (pintype "passive"))
    )
    (net (code "94") (name "unconnected-(STM2-NRST-Pad17)") (class "Default")
      (node (ref "STM2") (pin "17") (pinfunction "NRST_17") (pintype "passive"))
    )
    (net (code "95") (name "unconnected-(STM2-PC13-Pad2)") (class "Default")
      (node (ref "STM2") (pin "2") (pinfunction "PC13_2") (pintype "passive"))
    )
    (net (code "96") (name "unconnected-(STM2-VBAT-Pad1)") (class "Default")
      (node (ref "STM2") (pin "1") (pinfunction "VBAT_1") (pintype "passive"))
    )
    (net (code "97") (name "unconnected-(TMC_B-MS1-Pad12)") (class "Default")
      (node (ref "TMC_B") (pin "12") (pinfunction "MS1_12") (pintype "passive"))
    )
    (net (code "98") (name "unconnected-(TMC_B-MS2-Pad13)") (class "Default")
      (node (ref "TMC_B") (pin "13") (pinfunction "MS2_13") (pintype "passive"))
    )
    (net (code "99") (name "unconnected-(TMC_B-NC-Pad16)") (class "Default")
      (node (ref "TMC_B") (pin "16") (pinfunction "NC_16") (pintype "passive"))
    )
    (net (code "100") (name "unconnected-(TMC_B-RX-Pad15)") (class "Default")
      (node (ref "TMC_B") (pin "15") (pinfunction "RX_15") (pintype "passive"))
    )
    (net (code "101") (name "unconnected-(TMC_B-TX-Pad14)") (class "Default")
      (node (ref "TMC_B") (pin "14") (pinfunction "TX_14") (pintype "passive"))
    )
    (net (code "102") (name "unconnected-(TMC_B-null-Pad9)") (class "Default")
      (node (ref "TMC_B") (pin "9") (pinfunction "null_9") (pintype "passive"))
    )
    (net (code "103") (name "unconnected-(TMC_B-null-Pad10)") (class "Default")
      (node (ref "TMC_B") (pin "10") (pinfunction "null_10") (pintype "passive"))
    )
    (net (code "104") (name "unconnected-(TMC_C-MS1-Pad12)") (class "Default")
      (node (ref "TMC_C") (pin "12") (pinfunction "MS1_12") (pintype "passive"))
    )
    (net (code "105") (name "unconnected-(TMC_C-MS2-Pad13)") (class "Default")
      (node (ref "TMC_C") (pin "13") (pinfunction "MS2_13") (pintype "passive"))
    )
    (net (code "106") (name "unconnected-(TMC_C-NC-Pad16)") (class "Default")
      (node (ref "TMC_C") (pin "16") (pinfunction "NC_16") (pintype "passive"))
    )
    (net (code "107") (name "unconnected-(TMC_C-RX-Pad15)") (class "Default")
      (node (ref "TMC_C") (pin "15") (pinfunction "RX_15") (pintype "passive"))
    )
    (net (code "108") (name "unconnected-(TMC_C-TX-Pad14)") (class "Default")
      (node (ref "TMC_C") (pin "14") (pinfunction "TX_14") (pintype "passive"))
    )
    (net (code "109") (name "unconnected-(TMC_C-null-Pad9)") (class "Default")
      (node (ref "TMC_C") (pin "9") (pinfunction "null_9") (pintype "passive"))
    )
    (net (code "110") (name "unconnected-(TMC_C-null-Pad10)") (class "Default")
      (node (ref "TMC_C") (pin "10") (pinfunction "null_10") (pintype "passive"))
    )
    (net (code "111") (name "unconnected-(TMC_X-MS1-Pad12)") (class "Default")
      (node (ref "TMC_X") (pin "12") (pinfunction "MS1_12") (pintype "passive"))
    )
    (net (code "112") (name "unconnected-(TMC_X-MS2-Pad13)") (class "Default")
      (node (ref "TMC_X") (pin "13") (pinfunction "MS2_13") (pintype "passive"))
    )
    (net (code "113") (name "unconnected-(TMC_X-NC-Pad16)") (class "Default")
      (node (ref "TMC_X") (pin "16") (pinfunction "NC_16") (pintype "passive"))
    )
    (net (code "114") (name "unconnected-(TMC_X-RX-Pad15)") (class "Default")
      (node (ref "TMC_X") (pin "15") (pinfunction "RX_15") (pintype "passive"))
    )
    (net (code "115") (name "unconnected-(TMC_X-TX-Pad14)") (class "Default")
      (node (ref "TMC_X") (pin "14") (pinfunction "TX_14") (pintype "passive"))
    )
    (net (code "116") (name "unconnected-(TMC_X-null-Pad9)") (class "Default")
      (node (ref "TMC_X") (pin "9") (pinfunction "null_9") (pintype "passive"))
    )
    (net (code "117") (name "unconnected-(TMC_X-null-Pad10)") (class "Default")
      (node (ref "TMC_X") (pin "10") (pinfunction "null_10") (pintype "passive"))
    )
    (net (code "118") (name "unconnected-(TMC_Y-MS1-Pad12)") (class "Default")
      (node (ref "TMC_Y") (pin "12") (pinfunction "MS1_12") (pintype "passive"))
    )
    (net (code "119") (name "unconnected-(TMC_Y-MS2-Pad13)") (class "Default")
      (node (ref "TMC_Y") (pin "13") (pinfunction "MS2_13") (pintype "passive"))
    )
    (net (code "120") (name "unconnected-(TMC_Y-NC-Pad16)") (class "Default")
      (node (ref "TMC_Y") (pin "16") (pinfunction "NC_16") (pintype "passive"))
    )
    (net (code "121") (name "unconnected-(TMC_Y-RX-Pad15)") (class "Default")
      (node (ref "TMC_Y") (pin "15") (pinfunction "RX_15") (pintype "passive"))
    )
    (net (code "122") (name "unconnected-(TMC_Y-TX-Pad14)") (class "Default")
      (node (ref "TMC_Y") (pin "14") (pinfunction "TX_14") (pintype "passive"))
    )
    (net (code "123") (name "unconnected-(TMC_Y-null-Pad9)") (class "Default")
      (node (ref "TMC_Y") (pin "9") (pinfunction "null_9") (pintype "passive"))
    )
    (net (code "124") (name "unconnected-(TMC_Y-null-Pad10)") (class "Default")
      (node (ref "TMC_Y") (pin "10") (pinfunction "null_10") (pintype "passive"))
    )
    (net (code "125") (name "unconnected-(TMC_Z-MS2-Pad13)") (class "Default")
      (node (ref "TMC_Z") (pin "13") (pinfunction "MS2_13") (pintype "passive"))
    )
    (net (code "126") (name "unconnected-(TMC_Z-NC-Pad16)") (class "Default")
      (node (ref "TMC_Z") (pin "16") (pinfunction "NC_16") (pintype "passive"))
    )
    (net (code "127") (name "unconnected-(TMC_Z-RX-Pad15)") (class "Default")
      (node (ref "TMC_Z") (pin "15") (pinfunction "RX_15") (pintype "passive"))
    )
    (net (code "128") (name "unconnected-(TMC_Z-TX-Pad14)") (class "Default")
      (node (ref "TMC_Z") (pin "14") (pinfunction "TX_14") (pintype "passive"))
    )
    (net (code "129") (name "unconnected-(TMC_Z-null-Pad9)") (class "Default")
      (node (ref "TMC_Z") (pin "9") (pinfunction "null_9") (pintype "passive"))
    )
    (net (code "130") (name "unconnected-(TMC_Z-null-Pad10)") (class "Default")
      (node (ref "TMC_Z") (pin "10") (pinfunction "null_10") (pintype "passive"))
    )
  )
)
